# Adafruit_SPI_FRAM.net
KiCad netlist of a schematic drawn in EAGLE
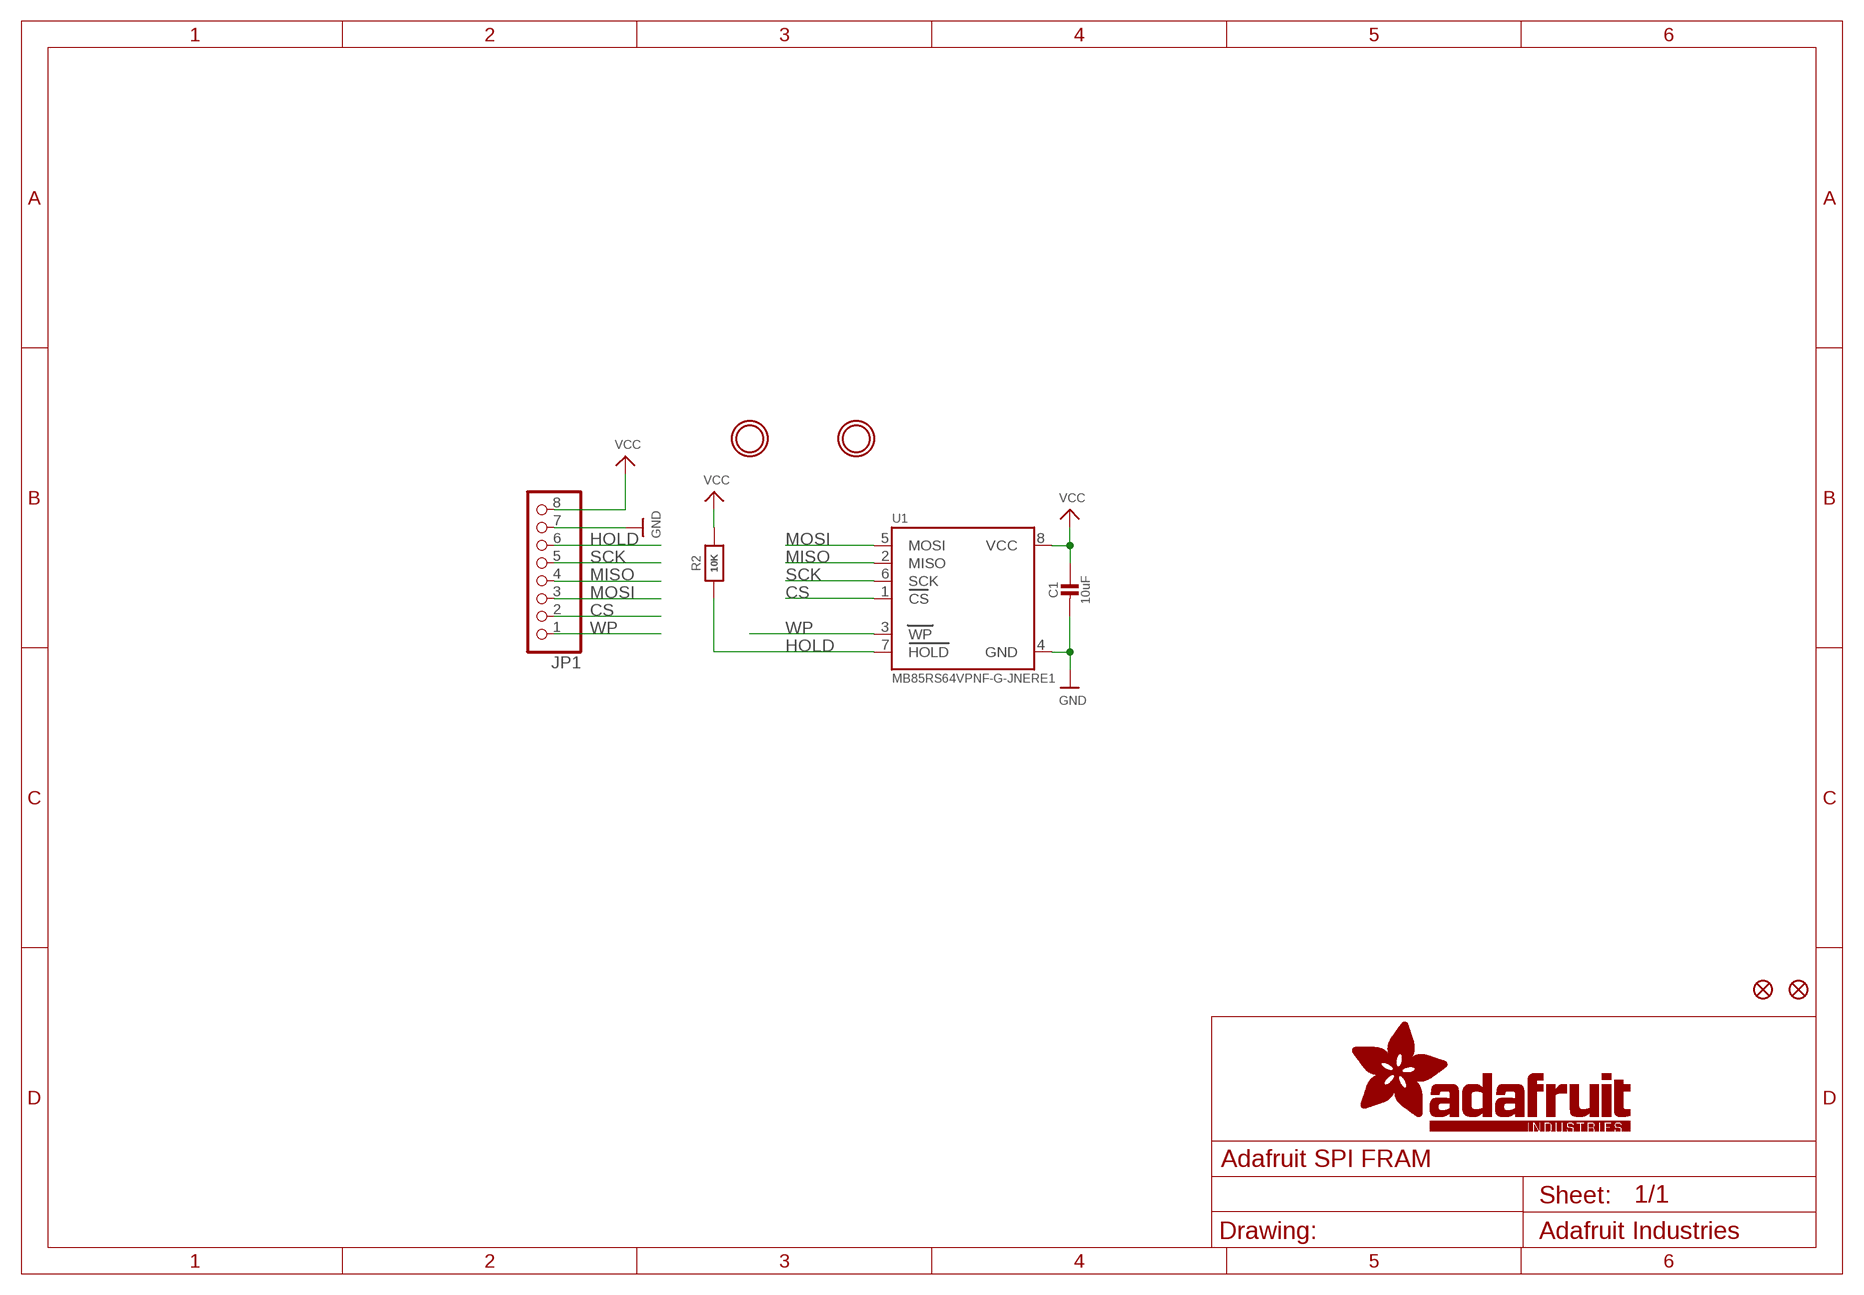
[diagram p0: schematic, sheet 1]

(export (version "E")
  (design (tool "Eeschema 10.0.6"))
  (components
    (comp (ref "C1")
      (value "10uF")
      (footprint "eagle-import:_0805MP")
      (libsource (lib "eagle-import") (part "CAP_CERAMIC_0805MP"))
    )
    (comp (ref "FID1")
      (value "FIDUCIAL\"\"")
      (footprint "eagle-import:FIDUCIAL_1MM")
      (libsource (lib "eagle-import") (part "FIDUCIAL{dblquote}{dblquote}"))
    )
    (comp (ref "FID2")
      (value "FIDUCIAL\"\"")
      (footprint "eagle-import:FIDUCIAL_1MM")
      (libsource (lib "eagle-import") (part "FIDUCIAL{dblquote}{dblquote}"))
    )
    (comp (ref "JP1")
      (value "HEADER-1X870MIL")
      (footprint "eagle-import:1X08_ROUND_70")
      (libsource (lib "eagle-import") (part "HEADER-1X870MIL"))
    )
    (comp (ref "R2")
      (value "10K")
      (footprint "eagle-import:_0805MP")
      (libsource (lib "eagle-import") (part "RESISTOR_0805MP"))
    )
    (comp (ref "U$5")
      (value "MOUNTINGHOLE2.5")
      (footprint "eagle-import:MOUNTINGHOLE_2.5_PLATED")
      (libsource (lib "eagle-import") (part "MOUNTINGHOLE2.5"))
    )
    (comp (ref "U$6")
      (value "MOUNTINGHOLE2.5")
      (footprint "eagle-import:MOUNTINGHOLE_2.5_PLATED")
      (libsource (lib "eagle-import") (part "MOUNTINGHOLE2.5"))
    )
    (comp (ref "U1")
      (value "MB85RS64VPNF-G-JNERE1")
      (footprint "eagle-import:SOIC8_150MIL")
      (libsource (lib "eagle-import") (part "FRAM_SOIC8_SPI"))
    )
  )
  (nets
    (net (code "1") (name "/CS") (class "Default")
      (node (ref "JP1") (pin "2") (pinfunction "2_2") (pintype "passive"))
      (node (ref "U1") (pin "1") (pinfunction "CS_1") (pintype "bidirectional"))
    )
    (net (code "2") (name "/HOLD") (class "Default")
      (node (ref "JP1") (pin "6") (pinfunction "6_6") (pintype "passive"))
      (node (ref "R2") (pin "1") (pinfunction "1_1") (pintype "passive"))
      (node (ref "U1") (pin "7") (pinfunction "HOLD_7") (pintype "bidirectional"))
    )
    (net (code "3") (name "/MISO") (class "Default")
      (node (ref "JP1") (pin "4") (pinfunction "4_4") (pintype "passive"))
      (node (ref "U1") (pin "2") (pinfunction "MISO_2") (pintype "bidirectional"))
    )
    (net (code "4") (name "/MOSI") (class "Default")
      (node (ref "JP1") (pin "3") (pinfunction "3_3") (pintype "passive"))
      (node (ref "U1") (pin "5") (pinfunction "MOSI_5") (pintype "bidirectional"))
    )
    (net (code "5") (name "/SCK") (class "Default")
      (node (ref "JP1") (pin "5") (pinfunction "5_5") (pintype "passive"))
      (node (ref "U1") (pin "6") (pinfunction "SCK_6") (pintype "bidirectional"))
    )
    (net (code "6") (name "/WP") (class "Default")
      (node (ref "JP1") (pin "1") (pinfunction "1_1") (pintype "passive"))
      (node (ref "U1") (pin "3") (pinfunction "WP_3") (pintype "bidirectional"))
    )
    (net (code "7") (name "GND") (class "Default")
      (node (ref "C1") (pin "2") (pinfunction "2_2") (pintype "passive"))
      (node (ref "JP1") (pin "7") (pinfunction "7_7") (pintype "passive"))
      (node (ref "U1") (pin "4") (pinfunction "GND_4") (pintype "power_in"))
    )
    (net (code "8") (name "VCC") (class "Default")
      (node (ref "C1") (pin "1") (pinfunction "1_1") (pintype "passive"))
      (node (ref "JP1") (pin "8") (pinfunction "8_8") (pintype "passive"))
      (node (ref "R2") (pin "2") (pinfunction "2_2") (pintype "passive"))
      (node (ref "U1") (pin "8") (pinfunction "VCC_8") (pintype "power_in"))
    )
  )
)
